# Module_Motor_DC.net
KiCad netlist of a schematic drawn in EAGLE
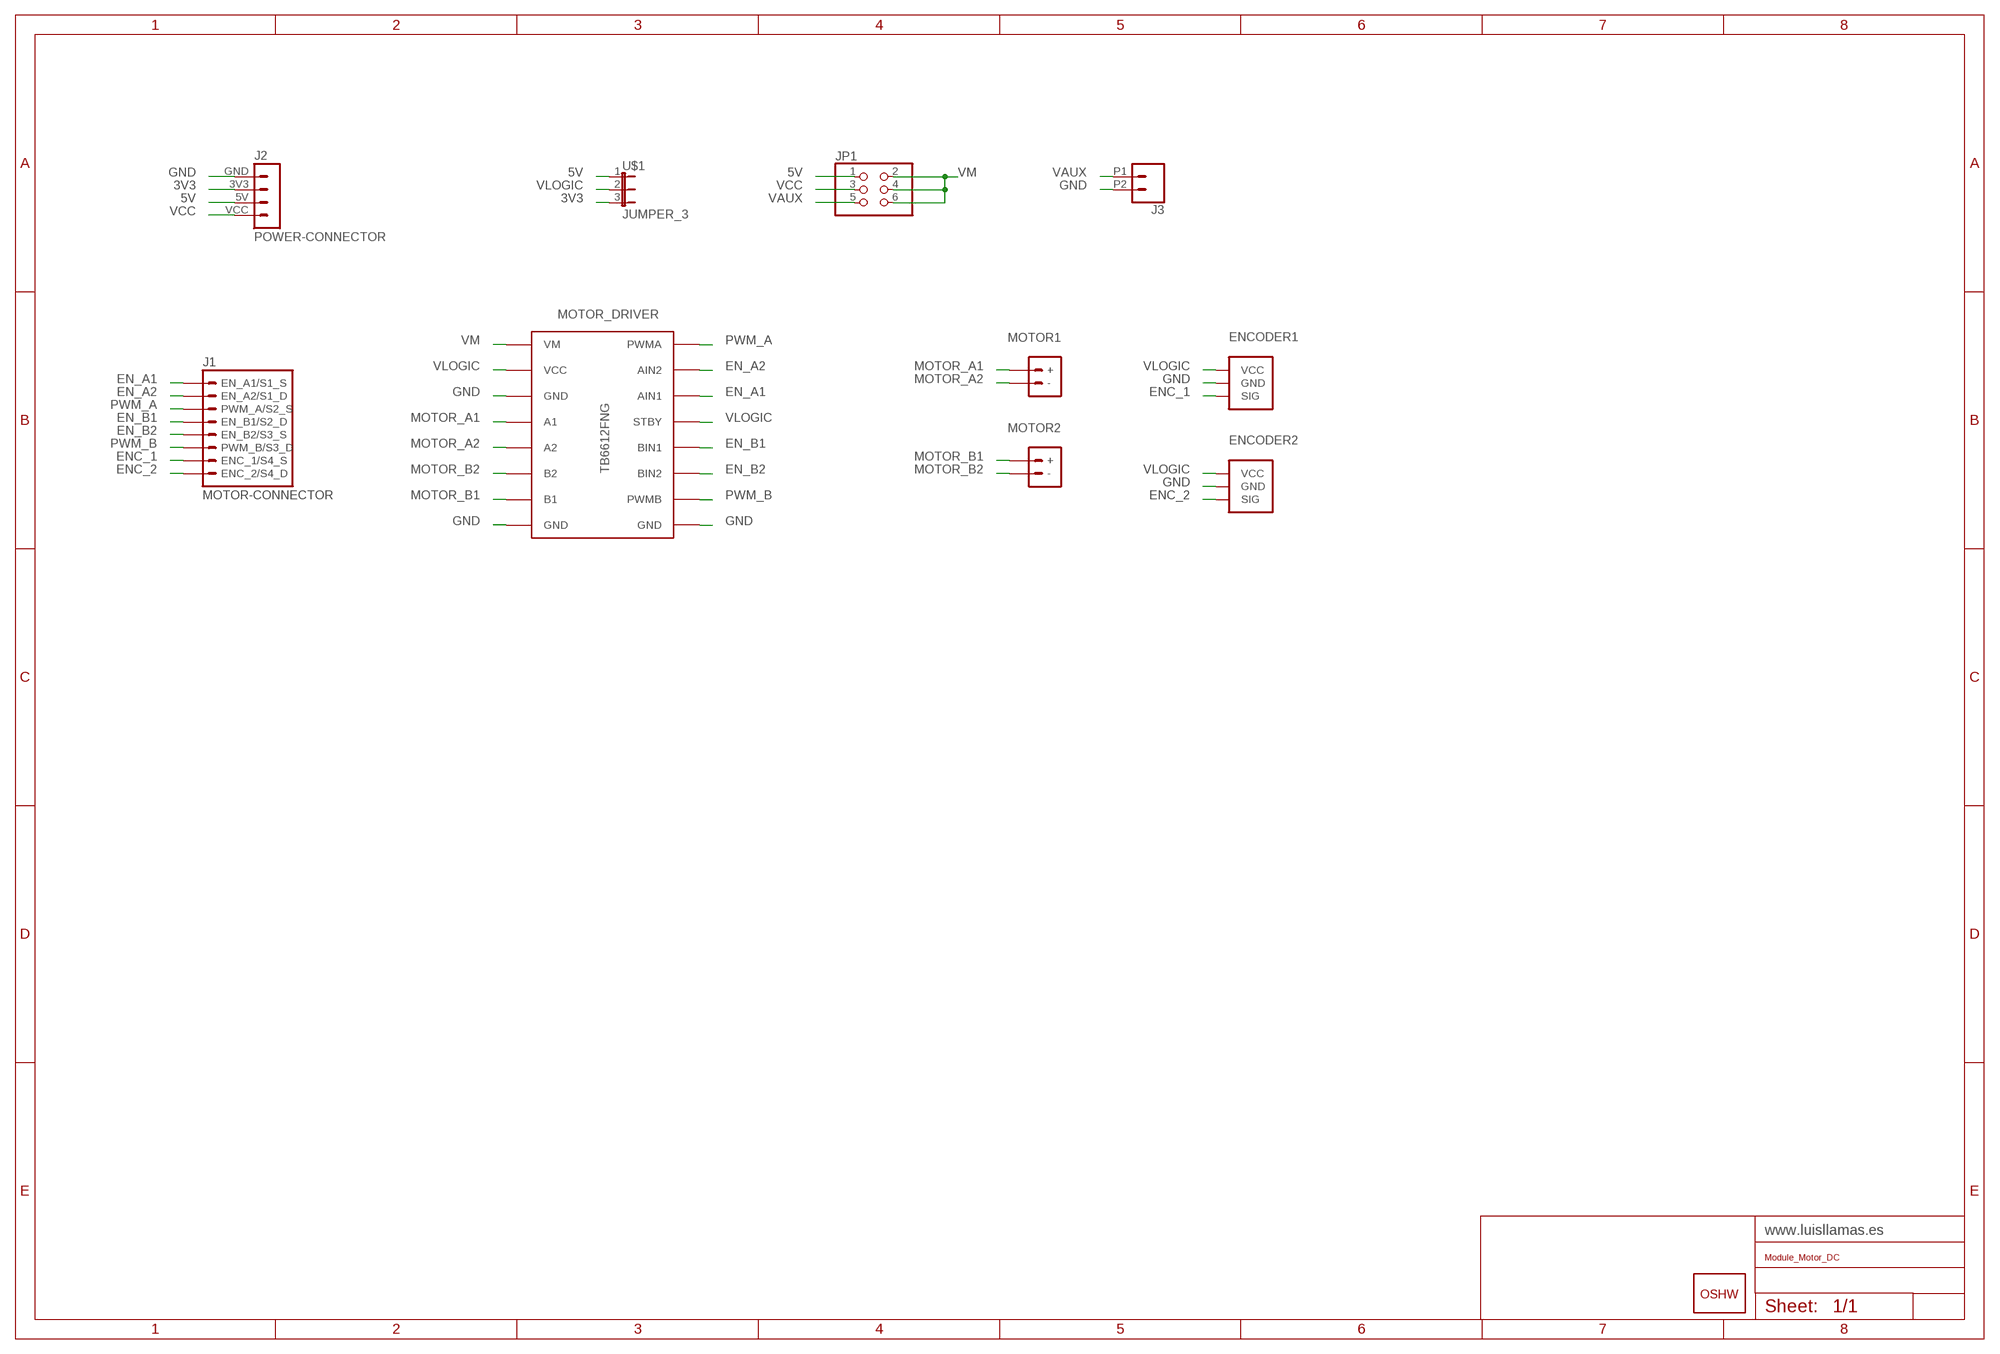
[diagram p0: schematic, sheet 1]

(export (version "E")
  (design (tool "Eeschema 10.0.6"))
  (components
    (comp (ref "ENCODER1")
      (value "ENCODER/OCT")
      (footprint "eagle-import:ENCODER")
      (libsource (lib "eagle-import") (part "ENCODER/OCT"))
    )
    (comp (ref "ENCODER2")
      (value "ENCODER/OCT")
      (footprint "eagle-import:ENCODER")
      (libsource (lib "eagle-import") (part "ENCODER/OCT"))
    )
    (comp (ref "GOLD_ORB_SM1")
      (value "OSHWLOGO_GOLD_ORB_MED")
      (footprint "eagle-import:OSHW1")
      (libsource (lib "eagle-import") (part "OSHWLOGO_GOLD_ORB_MED"))
    )
    (comp (ref "J1")
      (value "MOTOR-CONNECTOR")
      (footprint "eagle-import:MOTOR-CONNECTOR")
      (libsource (lib "eagle-import") (part "MOTOR-CONNECTOR"))
    )
    (comp (ref "J2")
      (value "POWER-CONNECTOR")
      (footprint "eagle-import:POWER-CONNECTOR")
      (libsource (lib "eagle-import") (part "POWER-CONNECTOR"))
    )
    (comp (ref "J3")
      (value "CONN_022.54MM_SCREWTERM")
      (footprint "eagle-import:1X02_2.54_SCREWTERM")
      (libsource (lib "eagle-import") (part "CONN_022.54MM_SCREWTERM"))
    )
    (comp (ref "JP1")
      (value "JUMPER_3X2/OCT")
      (footprint "eagle-import:JUMPER_3X2")
      (libsource (lib "eagle-import") (part "JUMPER_3X2/OCT"))
    )
    (comp (ref "MOTOR1")
      (value "MOTOR-TERMINAL5MM")
      (footprint "eagle-import:SCREWTERMINAL-5MM-2")
      (libsource (lib "eagle-import") (part "MOTOR-TERMINAL5MM"))
    )
    (comp (ref "MOTOR2")
      (value "MOTOR-TERMINAL5MM")
      (footprint "eagle-import:SCREWTERMINAL-5MM-2")
      (libsource (lib "eagle-import") (part "MOTOR-TERMINAL5MM"))
    )
    (comp (ref "MOTOR_DRIVER")
      (value "TB6612FNG")
      (footprint "eagle-import:TB6612FNG")
      (libsource (lib "eagle-import") (part "TB6612FNG"))
    )
    (comp (ref "U$1")
      (value "JUMPER_3")
      (footprint "eagle-import:JUMPER_3")
      (libsource (lib "eagle-import") (part "JUMPER_3"))
    )
  )
  (nets
    (net (code "1") (name "/3V3") (class "Default")
      (node (ref "J2") (pin "3V3") (pinfunction "3V3_3V3") (pintype "passive"))
      (node (ref "U$1") (pin "3") (pinfunction "3_3") (pintype "passive"))
    )
    (net (code "2") (name "/5V") (class "Default")
      (node (ref "J2") (pin "5V") (pinfunction "5V_5V") (pintype "passive"))
      (node (ref "JP1") (pin "1") (pinfunction "1_1") (pintype "passive"))
      (node (ref "U$1") (pin "1") (pinfunction "1_1") (pintype "passive"))
    )
    (net (code "3") (name "/ENC_1") (class "Default")
      (node (ref "ENCODER1") (pin "SIG") (pinfunction "SIG_SIG") (pintype "bidirectional"))
      (node (ref "J1") (pin "ENC_1/S4_S") (pinfunction "ENC_1/S4_S_ENC_1/S4_S") (pintype "passive"))
    )
    (net (code "4") (name "/ENC_2") (class "Default")
      (node (ref "ENCODER2") (pin "SIG") (pinfunction "SIG_SIG") (pintype "bidirectional"))
      (node (ref "J1") (pin "ENC_2/S4_D") (pinfunction "ENC_2/S4_D_ENC_2/S4_D") (pintype "passive"))
    )
    (net (code "5") (name "/EN_A1") (class "Default")
      (node (ref "J1") (pin "EN_A1/S1_S") (pinfunction "EN_A1/S1_S_EN_A1/S1_S") (pintype "passive"))
      (node (ref "MOTOR_DRIVER") (pin "AIN1") (pinfunction "AIN1_AIN1") (pintype "bidirectional"))
    )
    (net (code "6") (name "/EN_A2") (class "Default")
      (node (ref "J1") (pin "EN_A2/S1_D") (pinfunction "EN_A2/S1_D_EN_A2/S1_D") (pintype "passive"))
      (node (ref "MOTOR_DRIVER") (pin "AIN2") (pinfunction "AIN2_AIN2") (pintype "bidirectional"))
    )
    (net (code "7") (name "/EN_B1") (class "Default")
      (node (ref "J1") (pin "EN_B1/S2_D") (pinfunction "EN_B1/S2_D_EN_B1/S2_D") (pintype "passive"))
      (node (ref "MOTOR_DRIVER") (pin "BIN1") (pinfunction "BIN1_BIN1") (pintype "bidirectional"))
    )
    (net (code "8") (name "/EN_B2") (class "Default")
      (node (ref "J1") (pin "EN_B2/S3_S") (pinfunction "EN_B2/S3_S_EN_B2/S3_S") (pintype "passive"))
      (node (ref "MOTOR_DRIVER") (pin "BIN2") (pinfunction "BIN2_BIN2") (pintype "bidirectional"))
    )
    (net (code "9") (name "/GND") (class "Default")
      (node (ref "ENCODER1") (pin "GND") (pinfunction "GND_GND") (pintype "power_in"))
      (node (ref "ENCODER2") (pin "GND") (pinfunction "GND_GND") (pintype "power_in"))
      (node (ref "J2") (pin "GND") (pinfunction "GND_GND") (pintype "passive"))
      (node (ref "J3") (pin "P2") (pinfunction "2_P2") (pintype "passive"))
      (node (ref "MOTOR_DRIVER") (pin "GND1") (pinfunction "GND_GND1") (pintype "bidirectional"))
      (node (ref "MOTOR_DRIVER") (pin "GND2") (pinfunction "GND_GND2") (pintype "power_in"))
      (node (ref "MOTOR_DRIVER") (pin "GND3") (pinfunction "GND_GND3") (pintype "power_in"))
    )
    (net (code "10") (name "/MOTOR_A1") (class "Default")
      (node (ref "MOTOR1") (pin "+") (pinfunction "+_+") (pintype "passive"))
      (node (ref "MOTOR_DRIVER") (pin "A1") (pinfunction "A1_A1") (pintype "bidirectional"))
    )
    (net (code "11") (name "/MOTOR_A2") (class "Default")
      (node (ref "MOTOR1") (pin "-") (pinfunction "-_-") (pintype "passive"))
      (node (ref "MOTOR_DRIVER") (pin "A2") (pinfunction "A2_A2") (pintype "bidirectional"))
    )
    (net (code "12") (name "/MOTOR_B1") (class "Default")
      (node (ref "MOTOR2") (pin "+") (pinfunction "+_+") (pintype "passive"))
      (node (ref "MOTOR_DRIVER") (pin "B1") (pinfunction "B1_B1") (pintype "bidirectional"))
    )
    (net (code "13") (name "/MOTOR_B2") (class "Default")
      (node (ref "MOTOR2") (pin "-") (pinfunction "-_-") (pintype "passive"))
      (node (ref "MOTOR_DRIVER") (pin "B2") (pinfunction "B2_B2") (pintype "bidirectional"))
    )
    (net (code "14") (name "/PWM_A") (class "Default")
      (node (ref "J1") (pin "PWM_A/S2_S") (pinfunction "PWM_A/S2_S_PWM_A/S2_S") (pintype "passive"))
      (node (ref "MOTOR_DRIVER") (pin "PWMA") (pinfunction "PWMA_PWMA") (pintype "bidirectional"))
    )
    (net (code "15") (name "/PWM_B") (class "Default")
      (node (ref "J1") (pin "PWM_B/S3_D") (pinfunction "PWM_B/S3_D_PWM_B/S3_D") (pintype "passive"))
      (node (ref "MOTOR_DRIVER") (pin "PWMB") (pinfunction "PWMB_PWMB") (pintype "bidirectional"))
    )
    (net (code "16") (name "/VAUX") (class "Default")
      (node (ref "J3") (pin "P1") (pinfunction "1_P1") (pintype "passive"))
      (node (ref "JP1") (pin "5") (pinfunction "5_5") (pintype "passive"))
    )
    (net (code "17") (name "/VCC") (class "Default")
      (node (ref "J2") (pin "VCC") (pinfunction "VCC_VCC") (pintype "passive"))
      (node (ref "JP1") (pin "3") (pinfunction "3_3") (pintype "passive"))
    )
    (net (code "18") (name "/VLOGIC") (class "Default")
      (node (ref "ENCODER1") (pin "VCC") (pinfunction "VCC_VCC") (pintype "power_in"))
      (node (ref "ENCODER2") (pin "VCC") (pinfunction "VCC_VCC") (pintype "power_in"))
      (node (ref "MOTOR_DRIVER") (pin "STBY") (pinfunction "STBY_STBY") (pintype "bidirectional"))
      (node (ref "MOTOR_DRIVER") (pin "VCC") (pinfunction "VCC_VCC") (pintype "power_in"))
      (node (ref "U$1") (pin "2") (pinfunction "2_2") (pintype "passive"))
    )
    (net (code "19") (name "/VM") (class "Default")
      (node (ref "JP1") (pin "2") (pinfunction "2_2") (pintype "passive"))
      (node (ref "JP1") (pin "4") (pinfunction "4_4") (pintype "passive"))
      (node (ref "JP1") (pin "6") (pinfunction "6_6") (pintype "passive"))
      (node (ref "MOTOR_DRIVER") (pin "VM") (pinfunction "VM_VM") (pintype "power_in"))
    )
  )
)
